# ELEKTRA-BENCH_v0_1-20240103.net
KiCad netlist of a schematic drawn in EAGLE
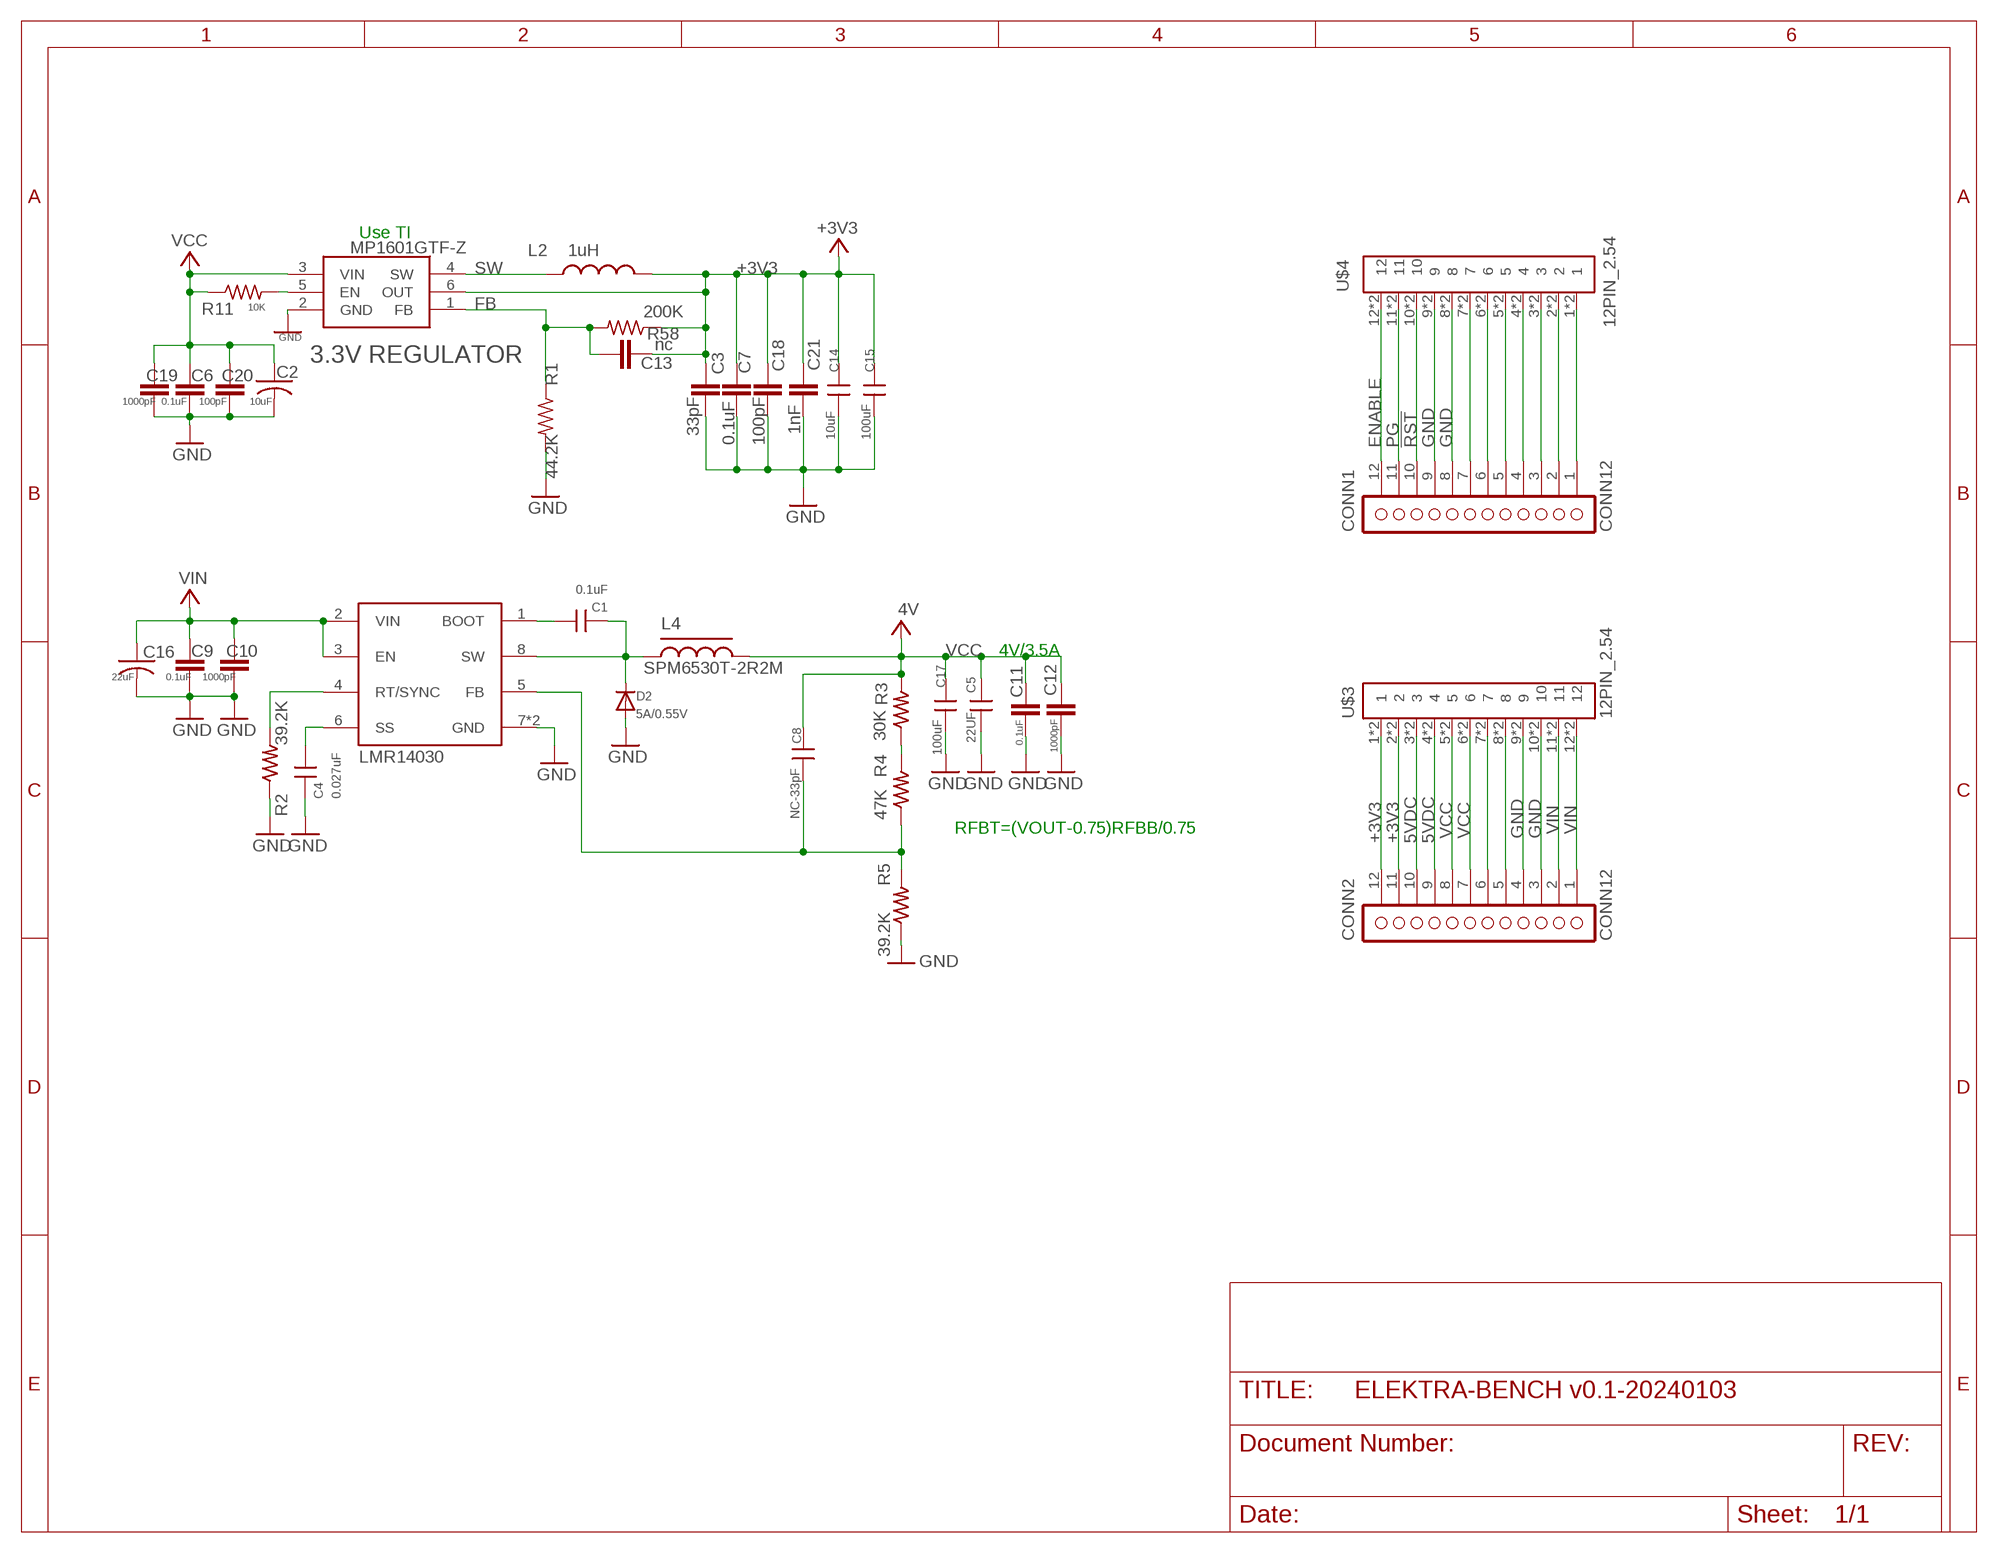
[diagram p0: schematic, sheet 1]

(export (version "E")
  (design (tool "Eeschema 10.0.6"))
  (components
    (comp (ref "C1")
      (value "0.1uF")
      (footprint "eagle-import:C0402")
      (libsource (lib "eagle-import") (part "particle SZ_21650216_CAP0402A"))
    )
    (comp (ref "C2")
      (value "10uF")
      (footprint "eagle-import:C0603_B")
      (libsource (lib "eagle-import") (part "C-US0603"))
    )
    (comp (ref "C3")
      (value "33pF")
      (footprint "eagle-import:C0402_B")
      (libsource (lib "eagle-import") (part "CAP_1"))
    )
    (comp (ref "C4")
      (value "0.027uF")
      (footprint "eagle-import:C0402")
      (libsource (lib "eagle-import") (part "particle SZ_21650216_CAP0402A"))
    )
    (comp (ref "C5")
      (value "22UF")
      (footprint "eagle-import:C0805")
      (libsource (lib "eagle-import") (part "CAPC0805"))
    )
    (comp (ref "C6")
      (value "0.1uF")
      (footprint "eagle-import:C0402_B")
      (libsource (lib "eagle-import") (part "CAP_1"))
    )
    (comp (ref "C7")
      (value "0.1uF")
      (footprint "eagle-import:C0402_B")
      (libsource (lib "eagle-import") (part "CAP_1"))
    )
    (comp (ref "C8")
      (value "NC-33pF")
      (footprint "eagle-import:C0402")
      (libsource (lib "eagle-import") (part "particle SZ_21650216_CAP0402A"))
    )
    (comp (ref "C9")
      (value "0.1uF")
      (footprint "eagle-import:C0402_B")
      (libsource (lib "eagle-import") (part "CAP_1"))
    )
    (comp (ref "C10")
      (value "1000pF")
      (footprint "eagle-import:C0402_B")
      (libsource (lib "eagle-import") (part "CAP_1"))
    )
    (comp (ref "C11")
      (value "0.1uF")
      (footprint "eagle-import:C0402_B")
      (libsource (lib "eagle-import") (part "CAP_1"))
    )
    (comp (ref "C12")
      (value "1000pF")
      (footprint "eagle-import:C0402_B")
      (libsource (lib "eagle-import") (part "CAP_1"))
    )
    (comp (ref "C13")
      (value "nc")
      (footprint "eagle-import:C0402_B")
      (libsource (lib "eagle-import") (part "CAP_1"))
    )
    (comp (ref "C14")
      (value "10uF")
      (footprint "eagle-import:C0805")
      (libsource (lib "eagle-import") (part "CAPC0805"))
    )
    (comp (ref "C15")
      (value "100uF")
      (footprint "eagle-import:C1206")
      (libsource (lib "eagle-import") (part "CAPC1206"))
    )
    (comp (ref "C16")
      (value "22uF")
      (footprint "eagle-import:C0603_B")
      (libsource (lib "eagle-import") (part "C-US0603"))
    )
    (comp (ref "C17")
      (value "100uF")
      (footprint "eagle-import:C1206")
      (libsource (lib "eagle-import") (part "CAPC1206"))
    )
    (comp (ref "C18")
      (value "100pF")
      (footprint "eagle-import:C0402_B")
      (libsource (lib "eagle-import") (part "CAP_1"))
    )
    (comp (ref "C19")
      (value "1000pF")
      (footprint "eagle-import:C0402_B")
      (libsource (lib "eagle-import") (part "CAP_1"))
    )
    (comp (ref "C20")
      (value "100pF")
      (footprint "eagle-import:C0402_B")
      (libsource (lib "eagle-import") (part "CAP_1"))
    )
    (comp (ref "C21")
      (value "1nF")
      (footprint "eagle-import:C0402_B")
      (libsource (lib "eagle-import") (part "CAP_1"))
    )
    (comp (ref "CONN1")
      (value "CONN12")
      (footprint "eagle-import:1X12_SMD_STRAIGHT")
      (libsource (lib "eagle-import") (part "CONN12"))
    )
    (comp (ref "CONN2")
      (value "CONN12")
      (footprint "eagle-import:1X12_SMD_STRAIGHT")
      (libsource (lib "eagle-import") (part "CONN12"))
    )
    (comp (ref "D2")
      (value "5A/0.55V")
      (footprint "eagle-import:SMADIODE")
      (libsource (lib "eagle-import") (part "DIODESMA"))
    )
    (comp (ref "L2")
      (value "1uH")
      (footprint "eagle-import:INDUCTOR-VLS-E")
      (libsource (lib "eagle-import") (part "INDUCTOR-SPARKFUNVLS3012ET-4R7M"))
    )
    (comp (ref "L4")
      (value "SPM6530T-2R2M")
      (footprint "eagle-import:INDCUTOR_SPM6530")
      (libsource (lib "eagle-import") (part "INDUCTOR"))
    )
    (comp (ref "R1")
      (value "44.2K")
      (footprint "eagle-import:R0402_B")
      (libsource (lib "eagle-import") (part "R-US_"))
    )
    (comp (ref "R2")
      (value "39.2K")
      (footprint "eagle-import:R-0402S")
      (libsource (lib "eagle-import") (part "RES0402S"))
    )
    (comp (ref "R3")
      (value "30K")
      (footprint "eagle-import:R-0402S")
      (libsource (lib "eagle-import") (part "RES0402S"))
    )
    (comp (ref "R4")
      (value "47K")
      (footprint "eagle-import:R-0402S")
      (libsource (lib "eagle-import") (part "RES0402S"))
    )
    (comp (ref "R5")
      (value "39.2K")
      (footprint "eagle-import:R-0402S")
      (libsource (lib "eagle-import") (part "RES0402S"))
    )
    (comp (ref "R11")
      (value "10K")
      (footprint "eagle-import:R0402_B")
      (libsource (lib "eagle-import") (part "Spark_R-US_"))
    )
    (comp (ref "R58")
      (value "200K")
      (footprint "eagle-import:R0402_B")
      (libsource (lib "eagle-import") (part "R-US_"))
    )
    (comp (ref "U$3")
      (value "12PIN_2.54")
      (footprint "eagle-import:12PIN_2.54")
      (libsource (lib "eagle-import") (part "12PIN_2.54"))
    )
    (comp (ref "U$4")
      (value "12PIN_2.54")
      (footprint "eagle-import:12PIN_2.54")
      (libsource (lib "eagle-import") (part "12PIN_2.54"))
    )
    (comp (ref "U2")
      (value "LMR14030")
      (footprint "eagle-import:SO_POWERPAD_8")
      (libsource (lib "eagle-import") (part "LMR14030"))
    )
    (comp (ref "U3")
      (value "MP1601GTF-Z")
      (footprint "eagle-import:SOTFL50P160X60-6N")
      (libsource (lib "eagle-import") (part "MP1601GTF-Z"))
    )
  )
  (nets
    (net (code "1") (name "+3V3") (class "Default")
      (node (ref "C13") (pin "1") (pinfunction "P$1_1") (pintype "passive"))
      (node (ref "C14") (pin "1") (pinfunction "1_1") (pintype "bidirectional"))
      (node (ref "C15") (pin "1") (pinfunction "1_1") (pintype "bidirectional"))
      (node (ref "C18") (pin "2") (pinfunction "P$2_2") (pintype "passive"))
      (node (ref "C21") (pin "2") (pinfunction "P$2_2") (pintype "passive"))
      (node (ref "C3") (pin "2") (pinfunction "P$2_2") (pintype "passive"))
      (node (ref "C7") (pin "2") (pinfunction "P$2_2") (pintype "passive"))
      (node (ref "CONN2") (pin "11") (pinfunction "11_11") (pintype "passive"))
      (node (ref "CONN2") (pin "12") (pinfunction "12_12") (pintype "passive"))
      (node (ref "L2") (pin "P$2") (pinfunction "2_P$2") (pintype "passive"))
      (node (ref "R58") (pin "1") (pinfunction "1_1") (pintype "passive"))
      (node (ref "U$3") (pin "1") (pinfunction "1_1") (pintype "bidirectional"))
      (node (ref "U$3") (pin "2") (pinfunction "2_2") (pintype "bidirectional"))
      (node (ref "U$3") (pin "P$1") (pinfunction "1_P$1") (pintype "bidirectional"))
      (node (ref "U$3") (pin "P$2") (pinfunction "2_P$2") (pintype "bidirectional"))
      (node (ref "U3") (pin "6") (pinfunction "OUT_6") (pintype "bidirectional"))
    )
    (net (code "2") (name "/5VDC") (class "Default")
      (node (ref "CONN2") (pin "10") (pinfunction "10_10") (pintype "passive"))
      (node (ref "CONN2") (pin "9") (pinfunction "9_9") (pintype "passive"))
      (node (ref "U$3") (pin "3") (pinfunction "3_3") (pintype "bidirectional"))
      (node (ref "U$3") (pin "4") (pinfunction "4_4") (pintype "bidirectional"))
      (node (ref "U$3") (pin "P$3") (pinfunction "3_P$3") (pintype "bidirectional"))
      (node (ref "U$3") (pin "P$4") (pinfunction "4_P$4") (pintype "bidirectional"))
    )
    (net (code "3") (name "/ENABLE") (class "Default")
      (node (ref "CONN1") (pin "12") (pinfunction "12_12") (pintype "passive"))
      (node (ref "U$4") (pin "12") (pinfunction "12_12") (pintype "bidirectional"))
      (node (ref "U$4") (pin "P$12") (pinfunction "12_P$12") (pintype "bidirectional"))
    )
    (net (code "4") (name "/FB") (class "Default")
      (node (ref "C13") (pin "2") (pinfunction "P$2_2") (pintype "passive"))
      (node (ref "R1") (pin "1") (pinfunction "1_1") (pintype "passive"))
      (node (ref "R58") (pin "2") (pinfunction "2_2") (pintype "passive"))
      (node (ref "U3") (pin "1") (pinfunction "FB_1") (pintype "bidirectional"))
    )
    (net (code "5") (name "/PG") (class "Default")
      (node (ref "CONN1") (pin "11") (pinfunction "11_11") (pintype "passive"))
      (node (ref "U$4") (pin "11") (pinfunction "11_11") (pintype "bidirectional"))
      (node (ref "U$4") (pin "P$11") (pinfunction "11_P$11") (pintype "bidirectional"))
    )
    (net (code "6") (name "/SW") (class "Default")
      (node (ref "L2") (pin "P$1") (pinfunction "1_P$1") (pintype "passive"))
      (node (ref "U3") (pin "4") (pinfunction "SW_4") (pintype "bidirectional"))
    )
    (net (code "7") (name "/~{RST}") (class "Default")
      (node (ref "CONN1") (pin "10") (pinfunction "10_10") (pintype "passive"))
      (node (ref "U$4") (pin "10") (pinfunction "10_10") (pintype "bidirectional"))
      (node (ref "U$4") (pin "P$10") (pinfunction "10_P$10") (pintype "bidirectional"))
    )
    (net (code "8") (name "4V") (class "Default")
      (node (ref "C11") (pin "2") (pinfunction "P$2_2") (pintype "passive"))
      (node (ref "C12") (pin "2") (pinfunction "P$2_2") (pintype "passive"))
      (node (ref "C17") (pin "1") (pinfunction "1_1") (pintype "bidirectional"))
      (node (ref "C19") (pin "2") (pinfunction "P$2_2") (pintype "passive"))
      (node (ref "C2") (pin "1") (pinfunction "1_1") (pintype "passive"))
      (node (ref "C20") (pin "2") (pinfunction "P$2_2") (pintype "passive"))
      (node (ref "C5") (pin "1") (pinfunction "1_1") (pintype "bidirectional"))
      (node (ref "C6") (pin "2") (pinfunction "P$2_2") (pintype "passive"))
      (node (ref "C8") (pin "2") (pinfunction "2_2") (pintype "bidirectional"))
      (node (ref "CONN2") (pin "7") (pinfunction "7_7") (pintype "passive"))
      (node (ref "CONN2") (pin "8") (pinfunction "8_8") (pintype "passive"))
      (node (ref "L4") (pin "2") (pinfunction "2_2") (pintype "bidirectional"))
      (node (ref "R11") (pin "1") (pinfunction "1_1") (pintype "passive"))
      (node (ref "R3") (pin "2") (pinfunction "2_2") (pintype "bidirectional"))
      (node (ref "U$3") (pin "5") (pinfunction "5_5") (pintype "bidirectional"))
      (node (ref "U$3") (pin "6") (pinfunction "6_6") (pintype "bidirectional"))
      (node (ref "U$3") (pin "P$5") (pinfunction "5_P$5") (pintype "bidirectional"))
      (node (ref "U$3") (pin "P$6") (pinfunction "6_P$6") (pintype "bidirectional"))
      (node (ref "U3") (pin "3") (pinfunction "VIN_3") (pintype "bidirectional"))
    )
    (net (code "9") (name "GND") (class "Default")
      (node (ref "C10") (pin "1") (pinfunction "P$1_1") (pintype "passive"))
      (node (ref "C11") (pin "1") (pinfunction "P$1_1") (pintype "passive"))
      (node (ref "C12") (pin "1") (pinfunction "P$1_1") (pintype "passive"))
      (node (ref "C14") (pin "2") (pinfunction "2_2") (pintype "bidirectional"))
      (node (ref "C15") (pin "2") (pinfunction "2_2") (pintype "bidirectional"))
      (node (ref "C16") (pin "2") (pinfunction "2_2") (pintype "passive"))
      (node (ref "C17") (pin "2") (pinfunction "2_2") (pintype "bidirectional"))
      (node (ref "C18") (pin "1") (pinfunction "P$1_1") (pintype "passive"))
      (node (ref "C19") (pin "1") (pinfunction "P$1_1") (pintype "passive"))
      (node (ref "C2") (pin "2") (pinfunction "2_2") (pintype "passive"))
      (node (ref "C20") (pin "1") (pinfunction "P$1_1") (pintype "passive"))
      (node (ref "C21") (pin "1") (pinfunction "P$1_1") (pintype "passive"))
      (node (ref "C3") (pin "1") (pinfunction "P$1_1") (pintype "passive"))
      (node (ref "C4") (pin "2") (pinfunction "2_2") (pintype "bidirectional"))
      (node (ref "C5") (pin "2") (pinfunction "2_2") (pintype "bidirectional"))
      (node (ref "C6") (pin "1") (pinfunction "P$1_1") (pintype "passive"))
      (node (ref "C7") (pin "1") (pinfunction "P$1_1") (pintype "passive"))
      (node (ref "C9") (pin "1") (pinfunction "P$1_1") (pintype "passive"))
      (node (ref "CONN1") (pin "8") (pinfunction "8_8") (pintype "passive"))
      (node (ref "CONN1") (pin "9") (pinfunction "9_9") (pintype "passive"))
      (node (ref "CONN2") (pin "3") (pinfunction "3_3") (pintype "passive"))
      (node (ref "CONN2") (pin "4") (pinfunction "4_4") (pintype "passive"))
      (node (ref "D2") (pin "A") (pinfunction "A_A") (pintype "passive"))
      (node (ref "R1") (pin "2") (pinfunction "2_2") (pintype "passive"))
      (node (ref "R2") (pin "1") (pinfunction "1_1") (pintype "bidirectional"))
      (node (ref "R5") (pin "1") (pinfunction "1_1") (pintype "bidirectional"))
      (node (ref "U$3") (pin "10") (pinfunction "10_10") (pintype "bidirectional"))
      (node (ref "U$3") (pin "9") (pinfunction "9_9") (pintype "bidirectional"))
      (node (ref "U$3") (pin "P$10") (pinfunction "10_P$10") (pintype "bidirectional"))
      (node (ref "U$3") (pin "P$9") (pinfunction "9_P$9") (pintype "bidirectional"))
      (node (ref "U$4") (pin "8") (pinfunction "8_8") (pintype "bidirectional"))
      (node (ref "U$4") (pin "9") (pinfunction "9_9") (pintype "bidirectional"))
      (node (ref "U$4") (pin "P$8") (pinfunction "8_P$8") (pintype "bidirectional"))
      (node (ref "U$4") (pin "P$9") (pinfunction "9_P$9") (pintype "bidirectional"))
      (node (ref "U2") (pin "7") (pinfunction "GND_7") (pintype "bidirectional"))
      (node (ref "U2") (pin "EP") (pinfunction "GND_EP") (pintype "bidirectional"))
      (node (ref "U3") (pin "2") (pinfunction "GND_2") (pintype "bidirectional"))
    )
    (net (code "10") (name "Net-(CONN1-Pad1)") (class "Default")
      (node (ref "CONN1") (pin "1") (pinfunction "1_1") (pintype "passive"))
      (node (ref "U$4") (pin "1") (pinfunction "1_1") (pintype "bidirectional"))
      (node (ref "U$4") (pin "P$1") (pinfunction "1_P$1") (pintype "bidirectional"))
    )
    (net (code "11") (name "Net-(CONN1-Pad2)") (class "Default")
      (node (ref "CONN1") (pin "2") (pinfunction "2_2") (pintype "passive"))
      (node (ref "U$4") (pin "2") (pinfunction "2_2") (pintype "bidirectional"))
      (node (ref "U$4") (pin "P$2") (pinfunction "2_P$2") (pintype "bidirectional"))
    )
    (net (code "12") (name "Net-(CONN1-Pad3)") (class "Default")
      (node (ref "CONN1") (pin "3") (pinfunction "3_3") (pintype "passive"))
      (node (ref "U$4") (pin "3") (pinfunction "3_3") (pintype "bidirectional"))
      (node (ref "U$4") (pin "P$3") (pinfunction "3_P$3") (pintype "bidirectional"))
    )
    (net (code "13") (name "Net-(CONN1-Pad4)") (class "Default")
      (node (ref "CONN1") (pin "4") (pinfunction "4_4") (pintype "passive"))
      (node (ref "U$4") (pin "4") (pinfunction "4_4") (pintype "bidirectional"))
      (node (ref "U$4") (pin "P$4") (pinfunction "4_P$4") (pintype "bidirectional"))
    )
    (net (code "14") (name "Net-(CONN1-Pad5)") (class "Default")
      (node (ref "CONN1") (pin "5") (pinfunction "5_5") (pintype "passive"))
      (node (ref "U$4") (pin "5") (pinfunction "5_5") (pintype "bidirectional"))
      (node (ref "U$4") (pin "P$5") (pinfunction "5_P$5") (pintype "bidirectional"))
    )
    (net (code "15") (name "Net-(CONN1-Pad6)") (class "Default")
      (node (ref "CONN1") (pin "6") (pinfunction "6_6") (pintype "passive"))
      (node (ref "U$4") (pin "6") (pinfunction "6_6") (pintype "bidirectional"))
      (node (ref "U$4") (pin "P$6") (pinfunction "6_P$6") (pintype "bidirectional"))
    )
    (net (code "16") (name "Net-(CONN1-Pad7)") (class "Default")
      (node (ref "CONN1") (pin "7") (pinfunction "7_7") (pintype "passive"))
      (node (ref "U$4") (pin "7") (pinfunction "7_7") (pintype "bidirectional"))
      (node (ref "U$4") (pin "P$7") (pinfunction "7_P$7") (pintype "bidirectional"))
    )
    (net (code "17") (name "Net-(CONN2-Pad5)") (class "Default")
      (node (ref "CONN2") (pin "5") (pinfunction "5_5") (pintype "passive"))
      (node (ref "U$3") (pin "8") (pinfunction "8_8") (pintype "bidirectional"))
      (node (ref "U$3") (pin "P$8") (pinfunction "8_P$8") (pintype "bidirectional"))
    )
    (net (code "18") (name "Net-(CONN2-Pad6)") (class "Default")
      (node (ref "CONN2") (pin "6") (pinfunction "6_6") (pintype "passive"))
      (node (ref "U$3") (pin "7") (pinfunction "7_7") (pintype "bidirectional"))
      (node (ref "U$3") (pin "P$7") (pinfunction "7_P$7") (pintype "bidirectional"))
    )
    (net (code "19") (name "Net-(R3-Pad1)") (class "Default")
      (node (ref "R3") (pin "1") (pinfunction "1_1") (pintype "bidirectional"))
      (node (ref "R4") (pin "2") (pinfunction "2_2") (pintype "bidirectional"))
    )
    (net (code "20") (name "Net-(U2-BOOT)") (class "Default")
      (node (ref "C1") (pin "1") (pinfunction "1_1") (pintype "bidirectional"))
      (node (ref "U2") (pin "1") (pinfunction "BOOT_1") (pintype "bidirectional"))
    )
    (net (code "21") (name "Net-(U2-FB)") (class "Default")
      (node (ref "C8") (pin "1") (pinfunction "1_1") (pintype "bidirectional"))
      (node (ref "R4") (pin "1") (pinfunction "1_1") (pintype "bidirectional"))
      (node (ref "R5") (pin "2") (pinfunction "2_2") (pintype "bidirectional"))
      (node (ref "U2") (pin "5") (pinfunction "FB_5") (pintype "bidirectional"))
    )
    (net (code "22") (name "Net-(U2-RT{slash}SYNC)") (class "Default")
      (node (ref "R2") (pin "2") (pinfunction "2_2") (pintype "bidirectional"))
      (node (ref "U2") (pin "4") (pinfunction "RT/SYNC_4") (pintype "bidirectional"))
    )
    (net (code "23") (name "Net-(U2-SS)") (class "Default")
      (node (ref "C4") (pin "1") (pinfunction "1_1") (pintype "bidirectional"))
      (node (ref "U2") (pin "6") (pinfunction "SS_6") (pintype "bidirectional"))
    )
    (net (code "24") (name "Net-(U2-SW)") (class "Default")
      (node (ref "C1") (pin "2") (pinfunction "2_2") (pintype "bidirectional"))
      (node (ref "D2") (pin "C") (pinfunction "C_C") (pintype "passive"))
      (node (ref "L4") (pin "1") (pinfunction "1_1") (pintype "bidirectional"))
      (node (ref "U2") (pin "8") (pinfunction "SW_8") (pintype "bidirectional"))
    )
    (net (code "25") (name "Net-(U3-EN)") (class "Default")
      (node (ref "R11") (pin "2") (pinfunction "2_2") (pintype "passive"))
      (node (ref "U3") (pin "5") (pinfunction "EN_5") (pintype "bidirectional"))
    )
    (net (code "26") (name "VIN") (class "Default")
      (node (ref "C10") (pin "2") (pinfunction "P$2_2") (pintype "passive"))
      (node (ref "C16") (pin "1") (pinfunction "1_1") (pintype "passive"))
      (node (ref "C9") (pin "2") (pinfunction "P$2_2") (pintype "passive"))
      (node (ref "CONN2") (pin "1") (pinfunction "1_1") (pintype "passive"))
      (node (ref "CONN2") (pin "2") (pinfunction "2_2") (pintype "passive"))
      (node (ref "U$3") (pin "11") (pinfunction "11_11") (pintype "bidirectional"))
      (node (ref "U$3") (pin "12") (pinfunction "12_12") (pintype "bidirectional"))
      (node (ref "U$3") (pin "P$11") (pinfunction "11_P$11") (pintype "bidirectional"))
      (node (ref "U$3") (pin "P$12") (pinfunction "12_P$12") (pintype "bidirectional"))
      (node (ref "U2") (pin "2") (pinfunction "VIN_2") (pintype "bidirectional"))
      (node (ref "U2") (pin "3") (pinfunction "EN_3") (pintype "bidirectional"))
    )
  )
)
